# amc7135-24mm-RGBW-led-driver-with-butt-m.net
KiCad netlist of a schematic drawn in EAGLE
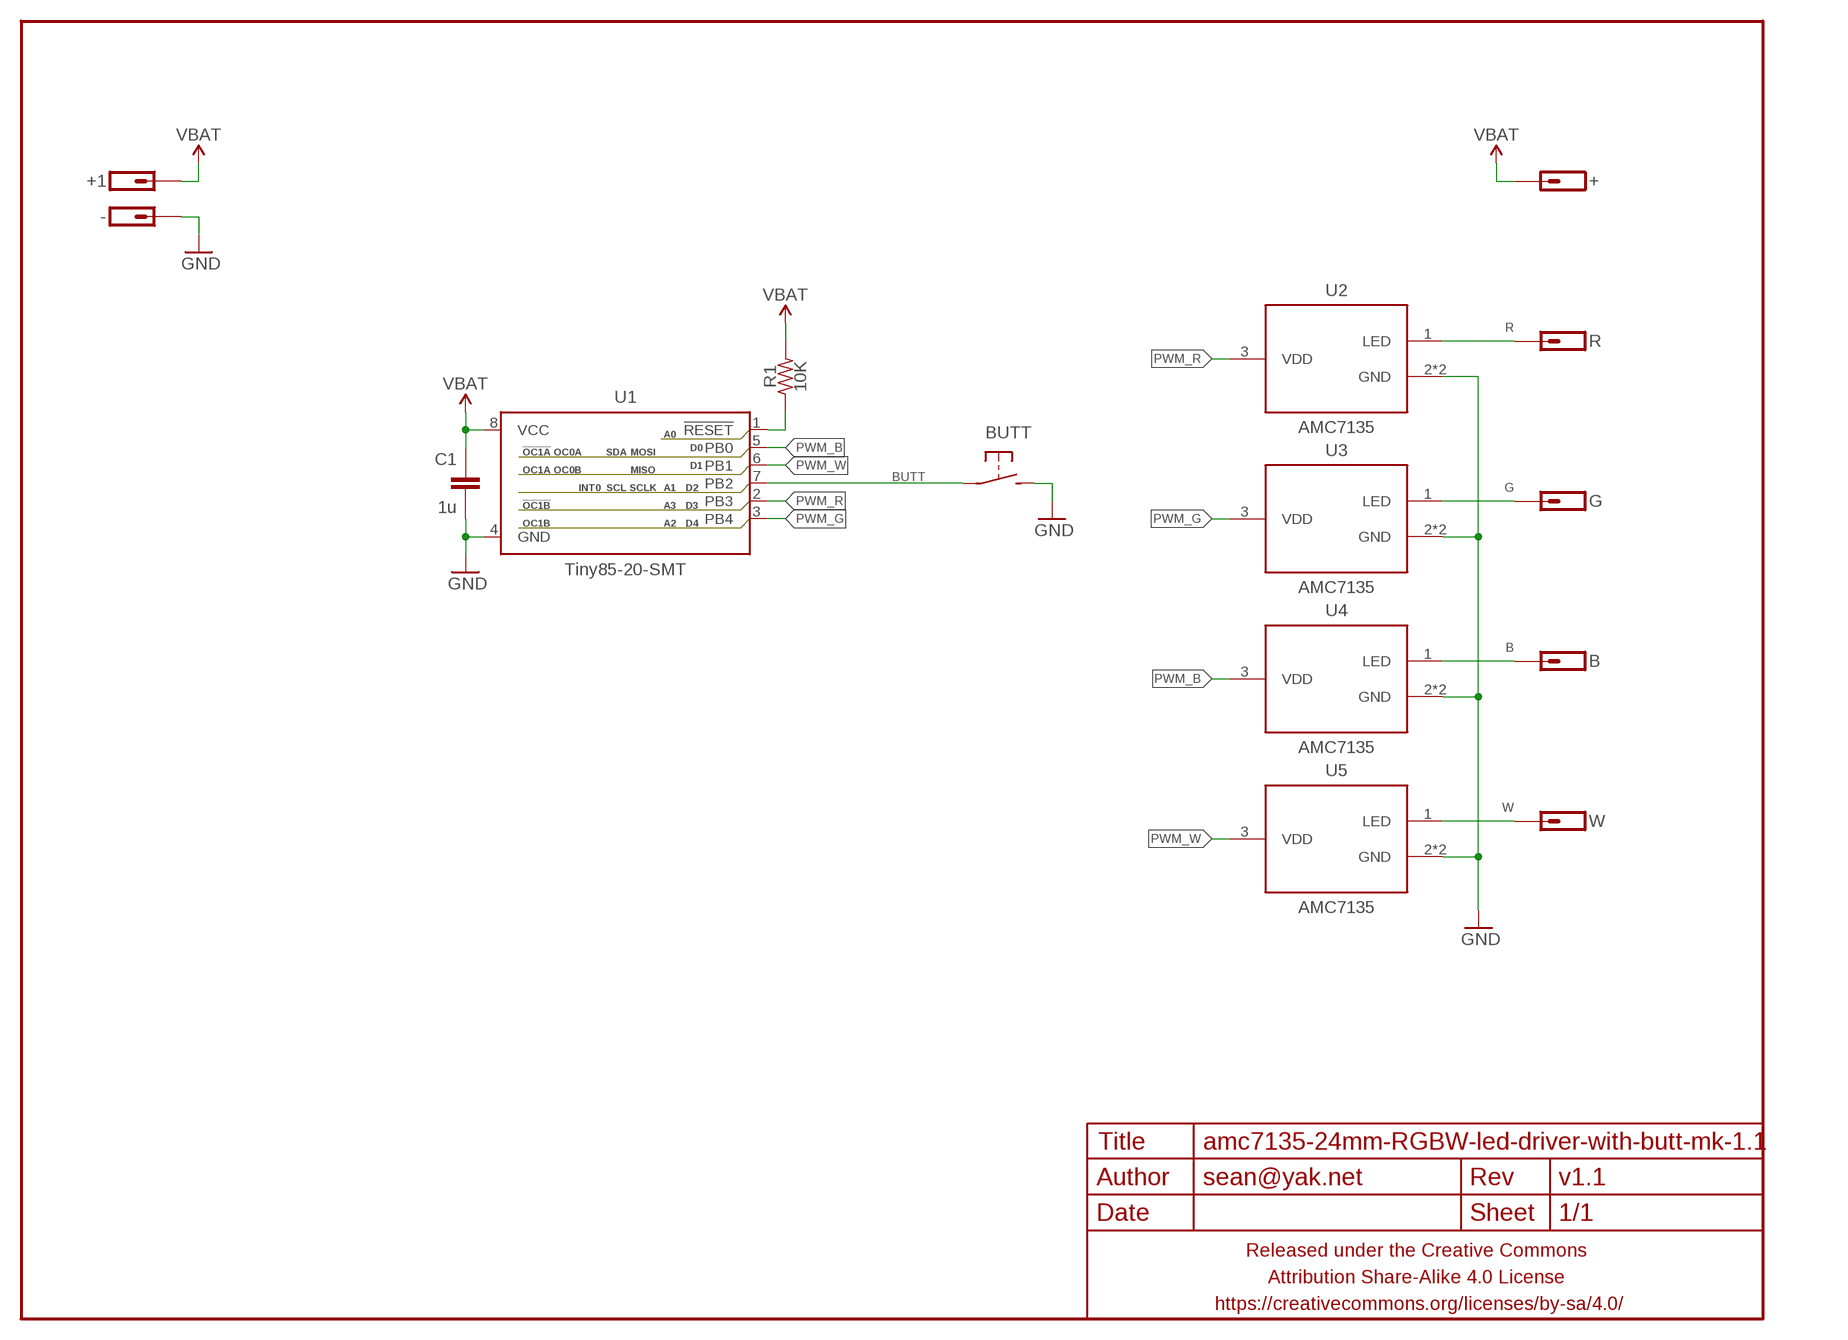
[diagram p0: schematic, sheet 1]

(export (version "E")
  (design (tool "Eeschema 10.0.6"))
  (components
    (comp (ref "+")
      (value "M01PTH-1.2MM-NS")
      (footprint "eagle-import:1X01-1.2MM-NS")
      (libsource (lib "eagle-import") (part "M01PTH-1.2MM-NS"))
    )
    (comp (ref "+1")
      (value "M01NOSTOP-CANTSTOP-DONTKNOWHOWTOSTOP")
      (footprint "eagle-import:1X01_SMD_NOSTOP_NOSILK")
      (libsource (lib "eagle-import") (part "M01NOSTOP-CANTSTOP-DONTKNOWHOWTOSTOP"))
    )
    (comp (ref "-")
      (value "M01NOT-A-VIA-NOPE")
      (footprint "eagle-import:1X01_NOSILK_NOSTOP")
      (libsource (lib "eagle-import") (part "M01NOT-A-VIA-NOPE"))
    )
    (comp (ref "B")
      (value "M01SMD-1.25MM-DIA")
      (footprint "eagle-import:1X01-SMD-1.25MM-DIA-NS")
      (libsource (lib "eagle-import") (part "M01SMD-1.25MM-DIA"))
    )
    (comp (ref "BUTT")
      (value "SPST-NO-TACT3MM-RA")
      (footprint "eagle-import:TACTILE-PTH-SIDE")
      (libsource (lib "eagle-import") (part "SPST-NO-TACT3MM-RA"))
    )
    (comp (ref "C1")
      (value "1u")
      (footprint "eagle-import:C0603-TIGHTER")
      (libsource (lib "eagle-import") (part "CAPACITOR-CERAMICC0603-TIGHTER"))
    )
    (comp (ref "FRAME1")
      (value "FRAME-LETTERNO_PACKAGE")
      (footprint "eagle-import:DUMMY")
      (fields (field (name "DESIGNER") "sean@yak.net") (field (name "VERSION") "v1.1"))
      (libsource (lib "eagle-import") (part "FRAME-LETTERNO_PACKAGE"))
    )
    (comp (ref "G")
      (value "M01SMD-1.25MM-DIA")
      (footprint "eagle-import:1X01-SMD-1.25MM-DIA-NS")
      (libsource (lib "eagle-import") (part "M01SMD-1.25MM-DIA"))
    )
    (comp (ref "R")
      (value "M01SMD-1.25MM-DIA")
      (footprint "eagle-import:1X01-SMD-1.25MM-DIA-NS")
      (libsource (lib "eagle-import") (part "M01SMD-1.25MM-DIA"))
    )
    (comp (ref "R1")
      (value "10K")
      (footprint "eagle-import:R0603-TIGHTER")
      (libsource (lib "eagle-import") (part "RESISTORR0603-TIGHTER"))
    )
    (comp (ref "U1")
      (value "Tiny85-20-SMT")
      (footprint "eagle-import:SO08-EIAJ")
      (libsource (lib "eagle-import") (part "ATTINY45TINY85-20-SOICW"))
    )
    (comp (ref "U2")
      (value "AMC7135")
      (footprint "eagle-import:SOT89")
      (libsource (lib "eagle-import") (part "AMC7135SOT-89"))
    )
    (comp (ref "U3")
      (value "AMC7135")
      (footprint "eagle-import:SOT89")
      (libsource (lib "eagle-import") (part "AMC7135SOT-89"))
    )
    (comp (ref "U4")
      (value "AMC7135")
      (footprint "eagle-import:SOT89")
      (libsource (lib "eagle-import") (part "AMC7135SOT-89"))
    )
    (comp (ref "U5")
      (value "AMC7135")
      (footprint "eagle-import:SOT89")
      (libsource (lib "eagle-import") (part "AMC7135SOT-89"))
    )
    (comp (ref "W")
      (value "M01SMD-1.25MM-DIA")
      (footprint "eagle-import:1X01-SMD-1.25MM-DIA-NS")
      (libsource (lib "eagle-import") (part "M01SMD-1.25MM-DIA"))
    )
  )
  (nets
    (net (code "1") (name "/B") (class "Default")
      (node (ref "B") (pin "P$1") (pinfunction "1_P$1") (pintype "passive"))
      (node (ref "U4") (pin "1") (pinfunction "LED_1") (pintype "bidirectional"))
    )
    (net (code "2") (name "/BUTT") (class "Default")
      (node (ref "BUTT") (pin "1") (pinfunction "1_1") (pintype "passive"))
      (node (ref "U1") (pin "7") (pinfunction "PB2_7") (pintype "bidirectional"))
    )
    (net (code "3") (name "/G") (class "Default")
      (node (ref "G") (pin "P$1") (pinfunction "1_P$1") (pintype "passive"))
      (node (ref "U3") (pin "1") (pinfunction "LED_1") (pintype "bidirectional"))
    )
    (net (code "4") (name "/R") (class "Default")
      (node (ref "R") (pin "P$1") (pinfunction "1_P$1") (pintype "passive"))
      (node (ref "U2") (pin "1") (pinfunction "LED_1") (pintype "bidirectional"))
    )
    (net (code "5") (name "/W") (class "Default")
      (node (ref "U5") (pin "1") (pinfunction "LED_1") (pintype "bidirectional"))
      (node (ref "W") (pin "P$1") (pinfunction "1_P$1") (pintype "passive"))
    )
    (net (code "6") (name "GND") (class "Default")
      (node (ref "-") (pin "P$1") (pinfunction "1_P$1") (pintype "passive"))
      (node (ref "BUTT") (pin "2") (pinfunction "2_2") (pintype "passive"))
      (node (ref "C1") (pin "2") (pinfunction "2_2") (pintype "passive"))
      (node (ref "U1") (pin "4") (pinfunction "GND_4") (pintype "bidirectional"))
      (node (ref "U2") (pin "2") (pinfunction "GND_2") (pintype "bidirectional"))
      (node (ref "U2") (pin "4") (pinfunction "GND_4") (pintype "bidirectional"))
      (node (ref "U3") (pin "2") (pinfunction "GND_2") (pintype "bidirectional"))
      (node (ref "U3") (pin "4") (pinfunction "GND_4") (pintype "bidirectional"))
      (node (ref "U4") (pin "2") (pinfunction "GND_2") (pintype "bidirectional"))
      (node (ref "U4") (pin "4") (pinfunction "GND_4") (pintype "bidirectional"))
      (node (ref "U5") (pin "2") (pinfunction "GND_2") (pintype "bidirectional"))
      (node (ref "U5") (pin "4") (pinfunction "GND_4") (pintype "bidirectional"))
    )
    (net (code "7") (name "Net-(U1-~{RESET})") (class "Default")
      (node (ref "R1") (pin "1") (pinfunction "1_1") (pintype "passive"))
      (node (ref "U1") (pin "1") (pinfunction "~{RESET}_1") (pintype "bidirectional"))
    )
    (net (code "8") (name "PWM_B") (class "Default")
      (node (ref "U1") (pin "5") (pinfunction "PB0_5") (pintype "bidirectional"))
      (node (ref "U4") (pin "3") (pinfunction "VDD_3") (pintype "bidirectional"))
    )
    (net (code "9") (name "PWM_G") (class "Default")
      (node (ref "U1") (pin "3") (pinfunction "PB4_3") (pintype "bidirectional"))
      (node (ref "U3") (pin "3") (pinfunction "VDD_3") (pintype "bidirectional"))
    )
    (net (code "10") (name "PWM_R") (class "Default")
      (node (ref "U1") (pin "2") (pinfunction "PB3_2") (pintype "bidirectional"))
      (node (ref "U2") (pin "3") (pinfunction "VDD_3") (pintype "bidirectional"))
    )
    (net (code "11") (name "PWM_W") (class "Default")
      (node (ref "U1") (pin "6") (pinfunction "PB1_6") (pintype "bidirectional"))
      (node (ref "U5") (pin "3") (pinfunction "VDD_3") (pintype "bidirectional"))
    )
    (net (code "12") (name "VBAT") (class "Default")
      (node (ref "+") (pin "P$1") (pinfunction "1_P$1") (pintype "passive"))
      (node (ref "+1") (pin "1") (pinfunction "1_1") (pintype "passive"))
      (node (ref "C1") (pin "1") (pinfunction "1_1") (pintype "passive"))
      (node (ref "R1") (pin "2") (pinfunction "2_2") (pintype "passive"))
      (node (ref "U1") (pin "8") (pinfunction "VCC_8") (pintype "bidirectional"))
    )
  )
)
